# 08_Ethernet.net
KiCad netlist of a schematic drawn in Altium Designer
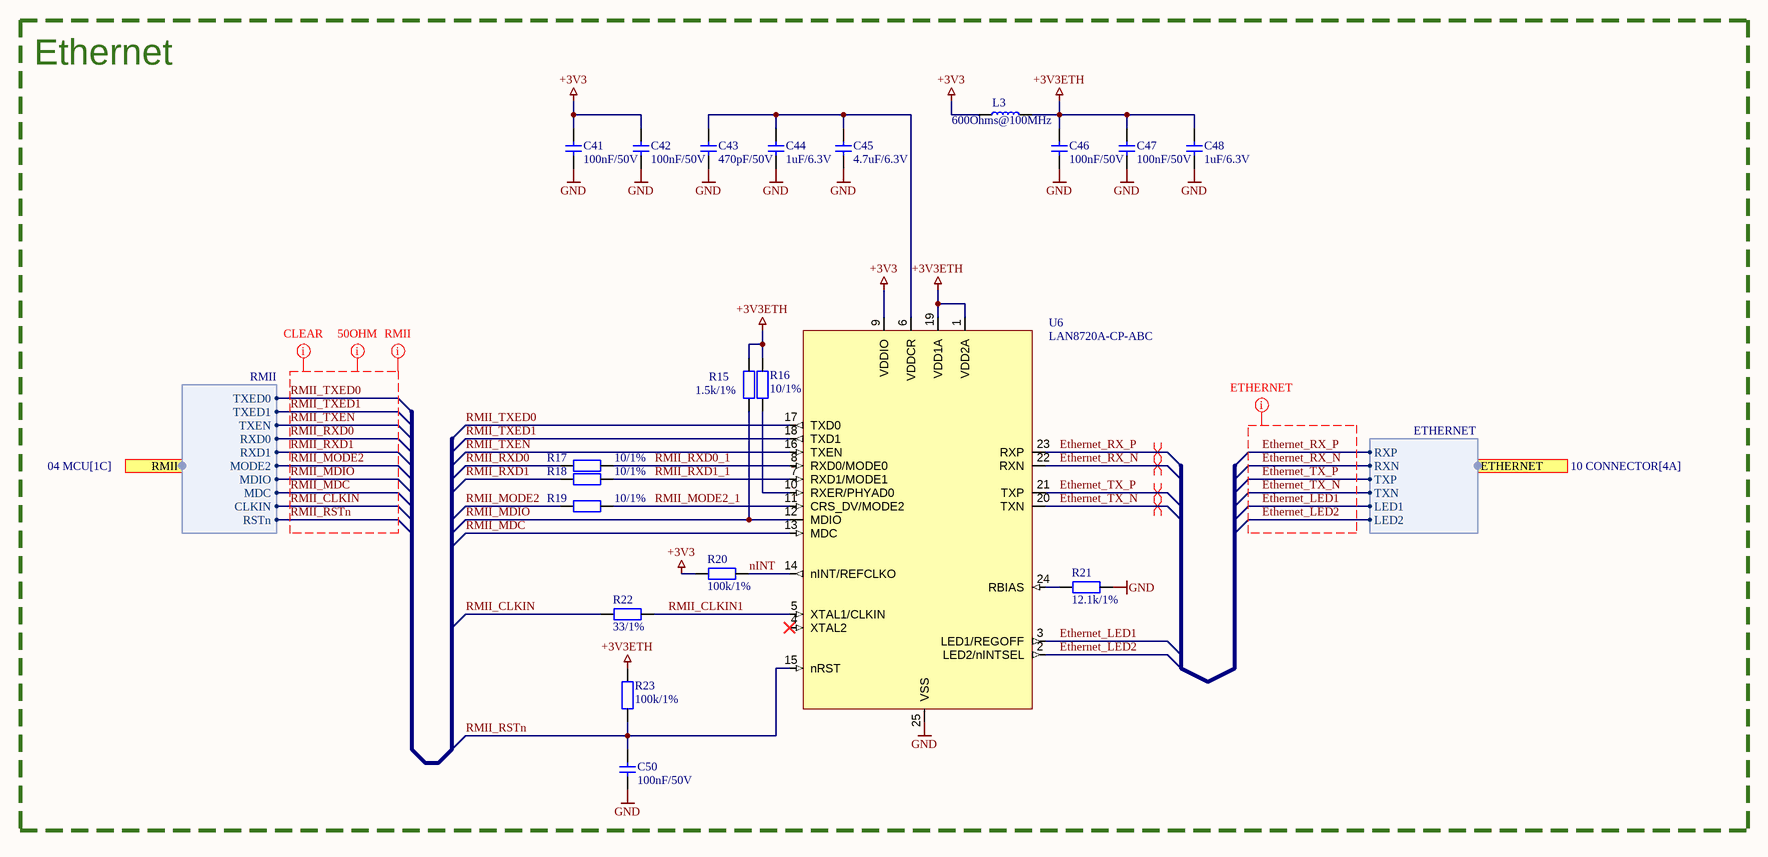
[diagram p0: 08 Ethernet.SchDoc]

(export (version "E")
  (design (tool "Eeschema 10.0.6"))
  (components
    (comp (ref "C41")
      (value "100nF/50V")
      (footprint "CAPC1005X06M-0402")
      (description "0.1 µF ±10% 50V Ceramic Capacitor X7R 0402 (1005 Metric)")
      (fields (field (name "MPN") "GRM155R71H104KE14D"))
      (libsource (lib "Symbol") (part "GRM155R71H104KE14D"))
    )
    (comp (ref "C42")
      (value "100nF/50V")
      (footprint "CAPC1005X06M-0402")
      (description "0.1 µF ±10% 50V Ceramic Capacitor X7R 0402 (1005 Metric)")
      (fields (field (name "MPN") "GRM155R71H104KE14D"))
      (libsource (lib "Symbol") (part "GRM155R71H104KE14D"))
    )
    (comp (ref "C43")
      (value "470pF/50V")
      (footprint "CAPC1005X06M-0402")
      (description "470 pF ±10% 50V Ceramic Capacitor X7R 0402 (1005 Metric)")
      (fields (field (name "MPN") "GRM155R71H471KA01D"))
      (libsource (lib "Symbol") (part "GRM155R71H471KA01D"))
    )
    (comp (ref "C44")
      (value "1uF/6.3V")
      (footprint "CAPC1005X06M-0402")
      (description "1 µF ±10% 6.3V Ceramic Capacitor X7R 0402 (1005 Metric)")
      (fields (field (name "MPN") "GRM155R70J105KA12J"))
      (libsource (lib "Symbol") (part "GRM155R70J105KA12J"))
    )
    (comp (ref "C45")
      (value "4.7uF/6.3V")
      (footprint "CAPC1005X06M-0402")
      (description "4.7 µF ±20% 6.3V Ceramic Capacitor X5R 0402 (1005 Metric)")
      (fields (field (name "MPN") "GRM155R60J475ME47D"))
      (libsource (lib "Symbol") (part "GRM155R60J475ME47D"))
    )
    (comp (ref "C46")
      (value "100nF/50V")
      (footprint "CAPC1005X06M-0402")
      (description "0.1 µF ±10% 50V Ceramic Capacitor X7R 0402 (1005 Metric)")
      (fields (field (name "MPN") "GRM155R71H104KE14D"))
      (libsource (lib "Symbol") (part "GRM155R71H104KE14D"))
    )
    (comp (ref "C47")
      (value "100nF/50V")
      (footprint "CAPC1005X06M-0402")
      (description "0.1 µF ±10% 50V Ceramic Capacitor X7R 0402 (1005 Metric)")
      (fields (field (name "MPN") "GRM155R71H104KE14D"))
      (libsource (lib "Symbol") (part "GRM155R71H104KE14D"))
    )
    (comp (ref "C48")
      (value "1uF/6.3V")
      (footprint "CAPC1005X06M-0402")
      (description "1 µF ±10% 6.3V Ceramic Capacitor X7R 0402 (1005 Metric)")
      (fields (field (name "MPN") "GRM155R70J105KA12J"))
      (libsource (lib "Symbol") (part "GRM155R70J105KA12J"))
    )
    (comp (ref "C50")
      (value "100nF/50V")
      (footprint "CAPC1005X06M-0402")
      (description "0.1 µF ±10% 50V Ceramic Capacitor X7R 0402 (1005 Metric)")
      (fields (field (name "MPN") "GRM155R71H104KE14D"))
      (libsource (lib "Symbol") (part "GRM155R71H104KE14D"))
    )
    (comp (ref "L3")
      (value "600Ohms@100MHz")
      (footprint "INDC1005X06M-0402")
      (description "600 Ohms @ 100 MHz 1 Ferrite Bead 0402 (1005 Metric) 300mA 520mOhm")
      (fields (field (name "MPN") "BLM15AG601SN1D"))
      (libsource (lib "Symbol") (part "BLM15AG601SN1D"))
    )
    (comp (ref "R15")
      (value "1.5k/1%")
      (footprint "RESC1005X04M-0402")
      (description "1.5 kOhms ±1% 0.063W, 1/16W Chip Resistor 0402 (1005 Metric) Moisture Resistant Thick Film")
      (fields (field (name "MPN") "RC0402FR-071K5L"))
      (libsource (lib "Symbol") (part "RC0402FR-071K5L"))
    )
    (comp (ref "R16")
      (value "10/1%")
      (footprint "RESC1005X04M-0402")
      (description "10 Ohms ±1% 0.063W, 1/16W Chip Resistor 0402 (1005 Metric) Moisture Resistant Thick Film")
      (fields (field (name "MPN") "RC0402FR-0710RL"))
      (libsource (lib "Symbol") (part "RC0402FR-0710RL"))
    )
    (comp (ref "R17")
      (value "10/1%")
      (footprint "RESC1005X04M-0402")
      (description "10 Ohms ±1% 0.063W, 1/16W Chip Resistor 0402 (1005 Metric) Moisture Resistant Thick Film")
      (fields (field (name "MPN") "RC0402FR-0710RL"))
      (libsource (lib "Symbol") (part "RC0402FR-0710RL"))
    )
    (comp (ref "R18")
      (value "10/1%")
      (footprint "RESC1005X04M-0402")
      (description "10 Ohms ±1% 0.063W, 1/16W Chip Resistor 0402 (1005 Metric) Moisture Resistant Thick Film")
      (fields (field (name "MPN") "RC0402FR-0710RL"))
      (libsource (lib "Symbol") (part "RC0402FR-0710RL"))
    )
    (comp (ref "R19")
      (value "10/1%")
      (footprint "RESC1005X04M-0402")
      (description "10 Ohms ±1% 0.063W, 1/16W Chip Resistor 0402 (1005 Metric) Moisture Resistant Thick Film")
      (fields (field (name "MPN") "RC0402FR-0710RL"))
      (libsource (lib "Symbol") (part "RC0402FR-0710RL"))
    )
    (comp (ref "R20")
      (value "100k/1%")
      (footprint "RESC1005X04M-0402")
      (description "100 kOhms ±1% 0.063W, 1/16W Chip Resistor 0402 (1005 Metric) Moisture Resistant Thick Film")
      (fields (field (name "MPN") "RC0402FR-07100KL"))
      (libsource (lib "Symbol") (part "RC0402FR-07100KL"))
    )
    (comp (ref "R21")
      (value "12.1k/1%")
      (footprint "RESC1005X04M-0402")
      (description "12.1 kOhms ±1% 0.063W, 1/16W Chip Resistor 0402 (1005 Metric) Moisture Resistant Thick Film")
      (fields (field (name "MPN") "RC0402FR-0712K1L"))
      (libsource (lib "Symbol") (part "RC0402FR-0712K1L"))
    )
    (comp (ref "R22")
      (value "33/1%")
      (footprint "RESC1005X04M-0402")
      (description "33 Ohms ±1% 0.063W, 1/16W Chip Resistor 0402 (1005 Metric) Moisture Resistant Thick Film")
      (fields (field (name "MPN") "RC0402FR-0733RL"))
      (libsource (lib "Symbol") (part "RC0402FR-0733RL"))
    )
    (comp (ref "R23")
      (value "100k/1%")
      (footprint "RESC1005X04M-0402")
      (description "100 kOhms ±1% 0.063W, 1/16W Chip Resistor 0402 (1005 Metric) Moisture Resistant Thick Film")
      (fields (field (name "MPN") "RC0402FR-07100KL"))
      (libsource (lib "Symbol") (part "RC0402FR-07100KL"))
    )
    (comp (ref "U6")
      (value "LAN8720A-CP-ABC")
      (footprint "QFN24P50_40X40X85L40X25")
      (description "2/2 Transceiver Full RMII 24-SQFN (4x4)")
      (libsource (lib "Symbol") (part "LAN8720A"))
    )
  )
  (nets
    (net (code "3") (name "+3V3") (class "Default")
      (node (ref "C41") (pin "2") (pinfunction "2_2") (pintype "passive"))
      (node (ref "C42") (pin "2") (pinfunction "2_2") (pintype "passive"))
      (node (ref "L3") (pin "1") (pinfunction "1_1") (pintype "passive"))
      (node (ref "R20") (pin "1") (pinfunction "1_1") (pintype "passive"))
      (node (ref "U6") (pin "9") (pinfunction "VDDIO_9") (pintype "power_in"))
    )
    (net (code "4") (name "+3V3ETH") (class "Default")
      (node (ref "C46") (pin "2") (pinfunction "2_2") (pintype "passive"))
      (node (ref "C47") (pin "2") (pinfunction "2_2") (pintype "passive"))
      (node (ref "C48") (pin "2") (pinfunction "2_2") (pintype "passive"))
      (node (ref "L3") (pin "2") (pinfunction "2_2") (pintype "passive"))
      (node (ref "R15") (pin "2") (pinfunction "2_2") (pintype "passive"))
      (node (ref "R16") (pin "2") (pinfunction "2_2") (pintype "passive"))
      (node (ref "R23") (pin "1") (pinfunction "1_1") (pintype "passive"))
      (node (ref "U6") (pin "1") (pinfunction "VDD2A_1") (pintype "power_in"))
      (node (ref "U6") (pin "19") (pinfunction "VDD1A_19") (pintype "power_in"))
    )
    (net (code "5") (name "/Ethernet_LED1") (class "Default")
      (node (ref "U6") (pin "3") (pinfunction "LED1/REGOFF_3") (pintype "output"))
    )
    (net (code "6") (name "/Ethernet_LED2") (class "Default")
      (node (ref "U6") (pin "2") (pinfunction "LED2/nINTSEL_2") (pintype "output"))
    )
    (net (code "7") (name "/Ethernet_RX_N") (class "Default")
      (node (ref "U6") (pin "22") (pinfunction "RXN_22") (pintype "bidirectional"))
    )
    (net (code "8") (name "/Ethernet_RX_P") (class "Default")
      (node (ref "U6") (pin "23") (pinfunction "RXP_23") (pintype "bidirectional"))
    )
    (net (code "9") (name "/Ethernet_TX_N") (class "Default")
      (node (ref "U6") (pin "20") (pinfunction "TXN_20") (pintype "bidirectional"))
    )
    (net (code "10") (name "/Ethernet_TX_P") (class "Default")
      (node (ref "U6") (pin "21") (pinfunction "TXP_21") (pintype "bidirectional"))
    )
    (net (code "11") (name "/RMII_CLKIN") (class "Default")
      (node (ref "R22") (pin "1") (pinfunction "1_1") (pintype "passive"))
    )
    (net (code "12") (name "/RMII_CLKIN1") (class "Default")
      (node (ref "R22") (pin "2") (pinfunction "2_2") (pintype "passive"))
      (node (ref "U6") (pin "5") (pinfunction "XTAL1/CLKIN_5") (pintype "input"))
    )
    (net (code "13") (name "/RMII_MDC") (class "Default")
      (node (ref "U6") (pin "13") (pinfunction "MDC_13") (pintype "input"))
    )
    (net (code "14") (name "/RMII_MDIO") (class "Default")
      (node (ref "R15") (pin "1") (pinfunction "1_1") (pintype "passive"))
      (node (ref "U6") (pin "12") (pinfunction "MDIO_12") (pintype "bidirectional"))
    )
    (net (code "15") (name "/RMII_MODE2") (class "Default")
      (node (ref "R19") (pin "1") (pinfunction "1_1") (pintype "passive"))
    )
    (net (code "16") (name "/RMII_MODE2_1") (class "Default")
      (node (ref "R19") (pin "2") (pinfunction "2_2") (pintype "passive"))
      (node (ref "U6") (pin "11") (pinfunction "CRS_DV/MODE2_11") (pintype "input"))
    )
    (net (code "17") (name "/RMII_RSTn") (class "Default")
      (node (ref "C50") (pin "2") (pinfunction "2_2") (pintype "passive"))
      (node (ref "R23") (pin "2") (pinfunction "2_2") (pintype "passive"))
      (node (ref "U6") (pin "15") (pinfunction "nRST_15") (pintype "input"))
    )
    (net (code "18") (name "/RMII_RXD0") (class "Default")
      (node (ref "R17") (pin "1") (pinfunction "1_1") (pintype "passive"))
    )
    (net (code "19") (name "/RMII_RXD0_1") (class "Default")
      (node (ref "R17") (pin "2") (pinfunction "2_2") (pintype "passive"))
      (node (ref "U6") (pin "8") (pinfunction "RXD0/MODE0_8") (pintype "input"))
    )
    (net (code "20") (name "/RMII_RXD1") (class "Default")
      (node (ref "R18") (pin "1") (pinfunction "1_1") (pintype "passive"))
    )
    (net (code "21") (name "/RMII_RXD1_1") (class "Default")
      (node (ref "R18") (pin "2") (pinfunction "2_2") (pintype "passive"))
      (node (ref "U6") (pin "7") (pinfunction "RXD1/MODE1_7") (pintype "input"))
    )
    (net (code "22") (name "/RMII_TXED0") (class "Default")
      (node (ref "U6") (pin "17") (pinfunction "TXD0_17") (pintype "output"))
    )
    (net (code "23") (name "/RMII_TXED1") (class "Default")
      (node (ref "U6") (pin "18") (pinfunction "TXD1_18") (pintype "output"))
    )
    (net (code "24") (name "/RMII_TXEN") (class "Default")
      (node (ref "U6") (pin "16") (pinfunction "TXEN_16") (pintype "input"))
    )
    (net (code "25") (name "/nINT") (class "Default")
      (node (ref "R20") (pin "2") (pinfunction "2_2") (pintype "passive"))
      (node (ref "U6") (pin "14") (pinfunction "nINT/REFCLKO_14") (pintype "output"))
    )
    (net (code "28") (name "GND") (class "Default")
      (node (ref "C41") (pin "1") (pinfunction "1_1") (pintype "passive"))
      (node (ref "C42") (pin "1") (pinfunction "1_1") (pintype "passive"))
      (node (ref "C43") (pin "1") (pinfunction "1_1") (pintype "passive"))
      (node (ref "C44") (pin "1") (pinfunction "1_1") (pintype "passive"))
      (node (ref "C45") (pin "1") (pinfunction "1_1") (pintype "passive"))
      (node (ref "C46") (pin "1") (pinfunction "1_1") (pintype "passive"))
      (node (ref "C47") (pin "1") (pinfunction "1_1") (pintype "passive"))
      (node (ref "C48") (pin "1") (pinfunction "1_1") (pintype "passive"))
      (node (ref "C50") (pin "1") (pinfunction "1_1") (pintype "passive"))
      (node (ref "R21") (pin "2") (pinfunction "2_2") (pintype "passive"))
      (node (ref "U6") (pin "25") (pinfunction "VSS_25") (pintype "power_in"))
    )
    (net (code "29") (name "Net-(U6-RBIAS)") (class "Default")
      (node (ref "R21") (pin "1") (pinfunction "1_1") (pintype "passive"))
      (node (ref "U6") (pin "24") (pinfunction "RBIAS_24") (pintype "input"))
    )
    (net (code "30") (name "Net-(U6-RXER{slash}PHYAD0)") (class "Default")
      (node (ref "R16") (pin "1") (pinfunction "1_1") (pintype "passive"))
      (node (ref "U6") (pin "10") (pinfunction "RXER/PHYAD0_10") (pintype "input"))
    )
    (net (code "31") (name "Net-(U6-VDDCR)") (class "Default")
      (node (ref "C43") (pin "2") (pinfunction "2_2") (pintype "passive"))
      (node (ref "C44") (pin "2") (pinfunction "2_2") (pintype "passive"))
      (node (ref "C45") (pin "2") (pinfunction "2_2") (pintype "passive"))
      (node (ref "U6") (pin "6") (pinfunction "VDDCR_6") (pintype "power_in"))
    )
    (net (code "32") (name "unconnected-(U6-XTAL2-Pad4)") (class "Default")
      (node (ref "U6") (pin "4") (pinfunction "XTAL2_4") (pintype "input+no_connect"))
    )
  )
)
